# usb.net
KiCad netlist of a schematic drawn in Altium Designer
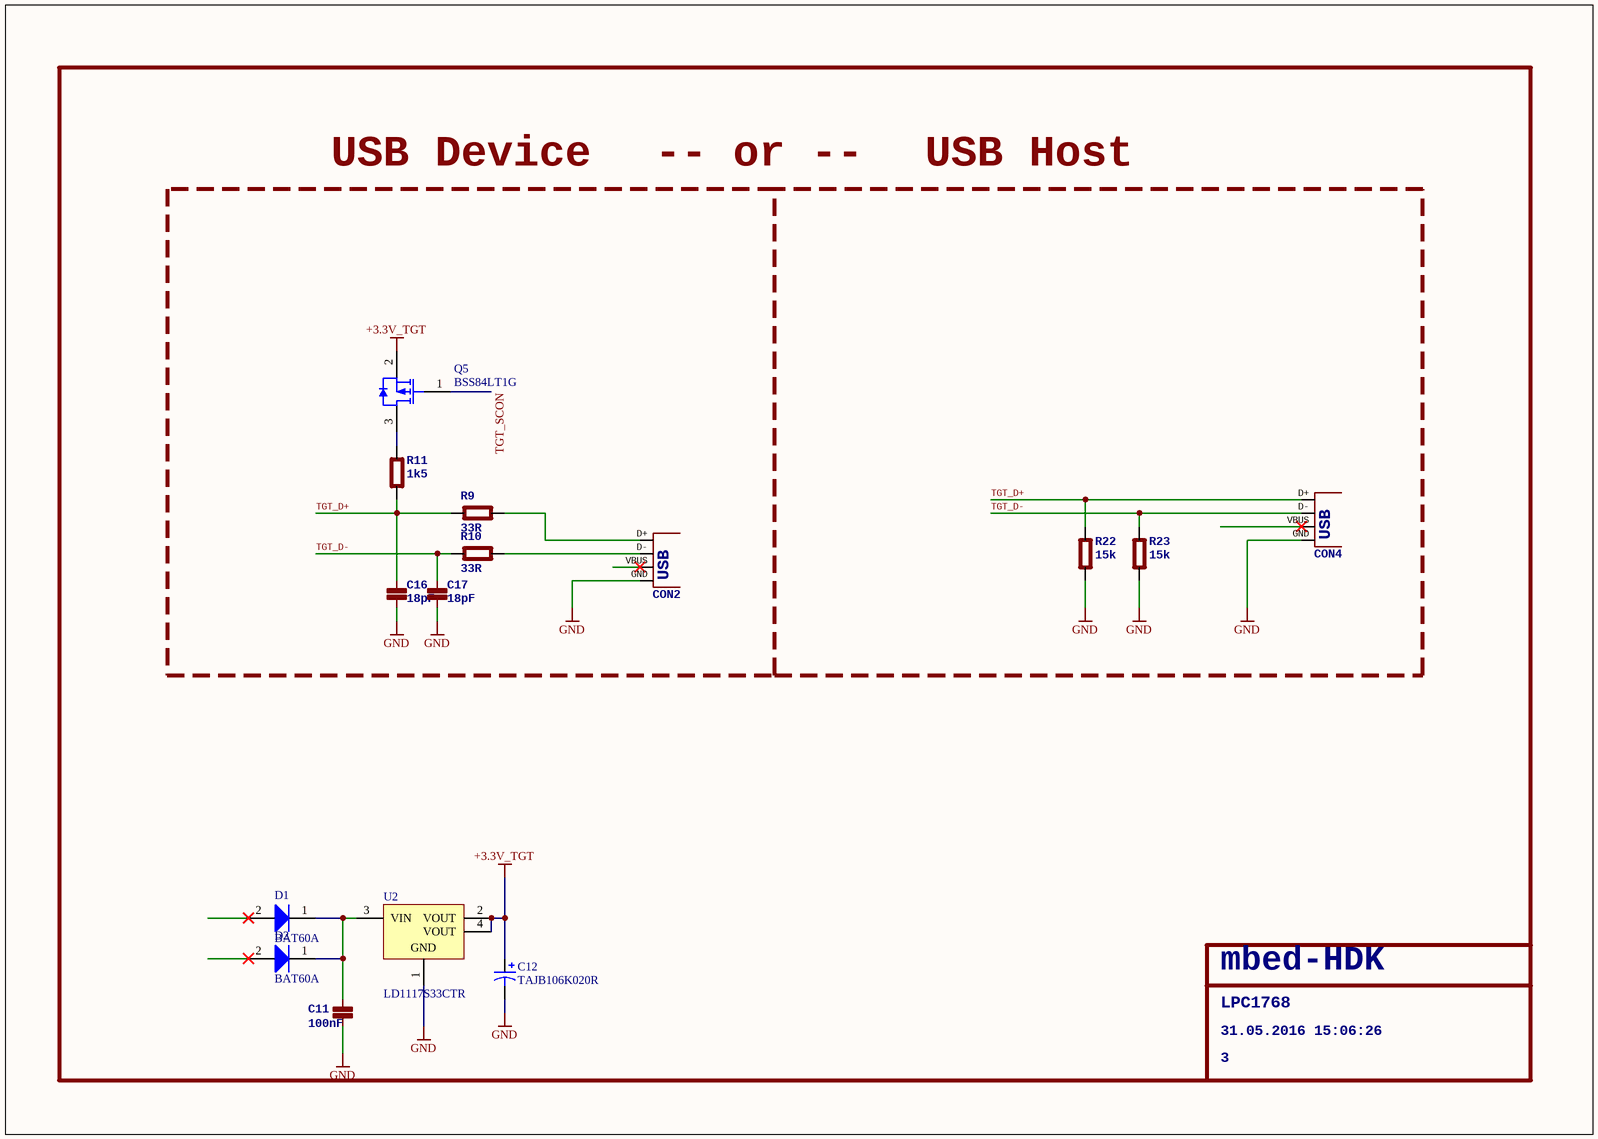
[diagram p0: usb.SchDoc]

(export (version "E")
  (design (tool "Eeschema 10.0.6"))
  (components
    (comp (ref "C11") (value "100nF") (footprint "0603") (libsource (lib "mbed-HDK") (part "C0603")))
    (comp (ref "C12")
      (value "TAJB106K020R")
      (footprint "AVX-CAPC3528_V")
      (description "Capacitor, Tantalum, 10uF 10% 20V MCCT-B (3528)")
      (fields (field (name "MANUFACTURER") "AVX") (field (name "TOLERANCE") "10%"))
      (libsource (lib "Altium Content Vault") (part "AVX-CAP-P-2"))
    )
    (comp (ref "C16") (value "18pF") (footprint "0603") (libsource (lib "mbed-HDK") (part "C0603")))
    (comp (ref "C17") (value "18pF") (footprint "0603") (libsource (lib "mbed-HDK") (part "C0603")))
    (comp (ref "CON2")
      (value "USB-MB-S")
      (footprint "USB-MB-S")
      (description "USB Connectors")
      (fields (field (name "USB") "USB"))
      (libsource (lib "mbed-HDK") (part "USB-MB-S"))
    )
    (comp (ref "CON4")
      (value "USB-A-H")
      (footprint "USB-A-H")
      (description "USB Connectors")
      (fields (field (name "USB") "USB"))
      (libsource (lib "mbed-HDK") (part "USB-A-H"))
    )
    (comp (ref "D1")
      (value "BAT60A")
      (footprint "INF-SOD323_V")
      (description "Silicon Schottky Diode, -55 to 85 degC, SOD323, Reel, Green")
      (fields (field (name "MANUFACTURER") "Infineon"))
      (libsource (lib "Altium Content Vault") (part "INF-D_K1A2-2"))
    )
    (comp (ref "D2")
      (value "BAT60A")
      (footprint "INF-SOD323_V")
      (description "Silicon Schottky Diode, -55 to 85 degC, SOD323, Reel, Green")
      (fields (field (name "MANUFACTURER") "Infineon"))
      (libsource (lib "Altium Content Vault") (part "INF-D_K1A2-2"))
    )
    (comp (ref "Q5")
      (value "BSS84LT1G")
      (footprint "ONSC-SOT-23-3-318-08_V")
      (description "Power MOSFET Single P-Channel, -50 V, 10 Ohm, 3-Pin SOT-23, Pb-Free, Tape and Reel")
      (fields (field (name "MANUFACTURER") "On Semiconductor"))
      (libsource (lib "Altium Content Vault") (part "ONSC-PMOS-G1S2D3-3_D"))
    )
    (comp (ref "R9") (value "33R") (footprint "0603") (libsource (lib "mbed-HDK") (part "R0603")))
    (comp (ref "R10") (value "33R") (footprint "0603") (libsource (lib "mbed-HDK") (part "R0603")))
    (comp (ref "R11") (value "1k5") (footprint "0603") (libsource (lib "mbed-HDK") (part "R0603")))
    (comp (ref "R22") (value "15k") (footprint "0603") (libsource (lib "mbed-HDK") (part "R0603")))
    (comp (ref "R23") (value "15k") (footprint "0603") (libsource (lib "mbed-HDK") (part "R0603")))
    (comp (ref "U2")
      (value "LD1117S33CTR")
      (footprint "SOT-223_L")
      (description "Fixed Low Drop Positive Voltage Regulator, 3.3V, 4-Pin SOT-223, Tape and Reel")
      (libsource (lib "Altium Content Vault") (part "PM-REG-LD1117-SOT4"))
    )
  )
  (nets
    (net (code "1") (name "+3.3V_TGT") (class "Default")
      (node (ref "C12") (pin "1") (pinfunction "1_1") (pintype "passive"))
      (node (ref "Q5") (pin "2") (pinfunction "S_2") (pintype "passive"))
      (node (ref "U2") (pin "2") (pinfunction "VOUT_2") (pintype "power_in"))
      (node (ref "U2") (pin "4") (pinfunction "VOUT_4") (pintype "power_in"))
    )
    (net (code "2") (name "/TGT_D+") (class "Default")
      (node (ref "C16") (pin "1") (pinfunction "P$1_1") (pintype "passive"))
      (node (ref "CON4") (pin "D+") (pinfunction "D+_D+") (pintype "passive"))
      (node (ref "R11") (pin "2") (pinfunction "P$2_2") (pintype "passive"))
      (node (ref "R22") (pin "2") (pinfunction "P$2_2") (pintype "passive"))
      (node (ref "R9") (pin "1") (pinfunction "P$1_1") (pintype "passive"))
    )
    (net (code "3") (name "/TGT_D-") (class "Default")
      (node (ref "C17") (pin "1") (pinfunction "P$1_1") (pintype "passive"))
      (node (ref "CON4") (pin "D-") (pinfunction "D-_D-") (pintype "passive"))
      (node (ref "R10") (pin "1") (pinfunction "P$1_1") (pintype "passive"))
      (node (ref "R23") (pin "2") (pinfunction "P$2_2") (pintype "passive"))
    )
    (net (code "4") (name "/TGT_SCON") (class "Default")
      (node (ref "Q5") (pin "1") (pinfunction "G_1") (pintype "passive"))
    )
    (net (code "5") (name "GND") (class "Default")
      (node (ref "C11") (pin "2") (pinfunction "P$2_2") (pintype "passive"))
      (node (ref "C12") (pin "2") (pinfunction "2_2") (pintype "passive"))
      (node (ref "C16") (pin "2") (pinfunction "P$2_2") (pintype "passive"))
      (node (ref "C17") (pin "2") (pinfunction "P$2_2") (pintype "passive"))
      (node (ref "CON2") (pin "GND") (pinfunction "GND_GND") (pintype "passive"))
      (node (ref "CON4") (pin "GND") (pinfunction "GND_GND") (pintype "passive"))
      (node (ref "R22") (pin "1") (pinfunction "P$1_1") (pintype "passive"))
      (node (ref "R23") (pin "1") (pinfunction "P$1_1") (pintype "passive"))
      (node (ref "U2") (pin "1") (pinfunction "GND_1") (pintype "power_in"))
    )
    (net (code "6") (name "Net-(C11-P$1)") (class "Default")
      (node (ref "C11") (pin "1") (pinfunction "P$1_1") (pintype "passive"))
      (node (ref "D1") (pin "1") (pinfunction "K_1") (pintype "passive"))
      (node (ref "D2") (pin "1") (pinfunction "K_1") (pintype "passive"))
      (node (ref "U2") (pin "3") (pinfunction "VIN_3") (pintype "power_in"))
    )
    (net (code "7") (name "Net-(Q5-D)") (class "Default")
      (node (ref "Q5") (pin "3") (pinfunction "D_3") (pintype "passive"))
      (node (ref "R11") (pin "1") (pinfunction "P$1_1") (pintype "passive"))
    )
    (net (code "8") (name "Net-(R9-P$2)") (class "Default")
      (node (ref "CON2") (pin "D+") (pinfunction "D+_D+") (pintype "passive"))
      (node (ref "R9") (pin "2") (pinfunction "P$2_2") (pintype "passive"))
    )
    (net (code "9") (name "Net-(R10-P$2)") (class "Default")
      (node (ref "CON2") (pin "D-") (pinfunction "D-_D-") (pintype "passive"))
      (node (ref "R10") (pin "2") (pinfunction "P$2_2") (pintype "passive"))
    )
    (net (code "10") (name "unconnected-(CON2-PadVBUS)") (class "Default")
      (node (ref "CON2") (pin "VBUS") (pinfunction "VBUS_VBUS") (pintype "passive+no_connect"))
    )
    (net (code "11") (name "unconnected-(CON4-PadVBUS)") (class "Default")
      (node (ref "CON4") (pin "VBUS") (pinfunction "VBUS_VBUS") (pintype "passive+no_connect"))
    )
    (net (code "12") (name "unconnected-(D1-A-Pad2)") (class "Default")
      (node (ref "D1") (pin "2") (pinfunction "A_2") (pintype "passive+no_connect"))
    )
    (net (code "13") (name "unconnected-(D2-A-Pad2)") (class "Default")
      (node (ref "D2") (pin "2") (pinfunction "A_2") (pintype "passive+no_connect"))
    )
  )
)
